# BAT_Simulator.net
KiCad netlist of a schematic drawn in Altium Designer
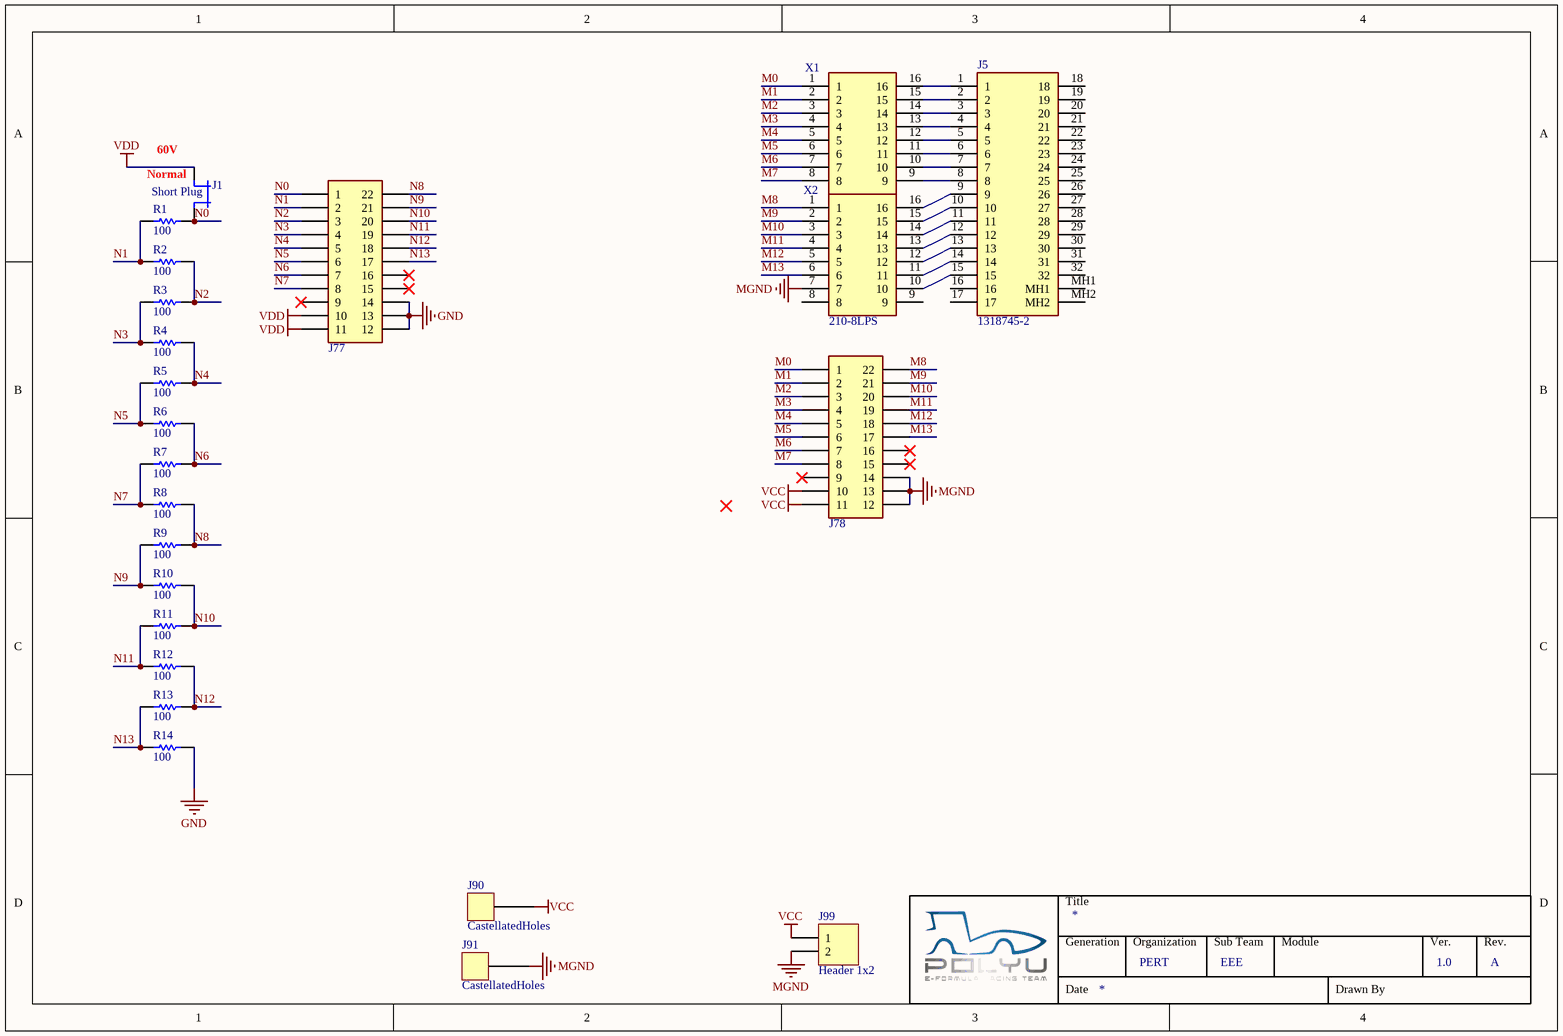
[diagram p0: BAT_Simulator.SchDoc]

(export (version "E")
  (design (tool "Eeschema 10.0.6"))
  (components
    (comp (ref "J1")
      (value "Short Plug")
      (footprint "HDR_1X2_2.54_THD")
      (description "Jumper for shorting two net")
      (libsource (lib "BMS_ShareComponentLibrary") (part "Jumper"))
    )
    (comp (ref "J5")
      (value "1318745-2")
      (footprint "TH025_32P")
      (fields (field (name "MOUSER PART NUMBER") "571-1318745-2"))
      (libsource (lib "BMS_ShareComponentLibrary") (part "TE TH/.25 32P TH"))
    )
    (comp (ref "J77")
      (value "Header 1x5")
      (footprint "HDR_2x11_2.54_THD")
      (description "Header 2x11")
      (libsource (lib "BMS_ShareComponentLibrary") (part "Header 2x11"))
    )
    (comp (ref "J78")
      (value "Header 1x5")
      (footprint "HDR_2x11_2.54_THD")
      (description "Header 2x11")
      (libsource (lib "BMS_ShareComponentLibrary") (part "Header 2x11"))
    )
    (comp (ref "J90")
      (value "CastellatedHoles")
      (footprint "CastellatedHole")
      (libsource (lib "BMS_ShareComponentLibrary") (part "CastellatedHoles"))
    )
    (comp (ref "J91")
      (value "CastellatedHoles")
      (footprint "CastellatedHole")
      (libsource (lib "BMS_ShareComponentLibrary") (part "CastellatedHoles"))
    )
    (comp (ref "J99")
      (value "Header 1x2")
      (footprint "HDR_1X2_2.54_THD")
      (description "Header, 2-Pin")
      (libsource (lib "BMS_ShareComponentLibrary") (part "Header 1x2"))
    )
    (comp (ref "R1")
      (value "100")
      (footprint "2512_SMD_R")
      (description "2512 SMD Resistor")
      (fields (field (name "TOLERANCE") "1%"))
      (libsource (lib "BMS_ShareComponentLibrary") (part "2512_SMD_Resistor"))
    )
    (comp (ref "R2")
      (value "100")
      (footprint "2512_SMD_R")
      (description "2512 SMD Resistor")
      (fields (field (name "TOLERANCE") "1%"))
      (libsource (lib "BMS_ShareComponentLibrary") (part "2512_SMD_Resistor"))
    )
    (comp (ref "R3")
      (value "100")
      (footprint "2512_SMD_R")
      (description "2512 SMD Resistor")
      (fields (field (name "TOLERANCE") "1%"))
      (libsource (lib "BMS_ShareComponentLibrary") (part "2512_SMD_Resistor"))
    )
    (comp (ref "R4")
      (value "100")
      (footprint "2512_SMD_R")
      (description "2512 SMD Resistor")
      (fields (field (name "TOLERANCE") "1%"))
      (libsource (lib "BMS_ShareComponentLibrary") (part "2512_SMD_Resistor"))
    )
    (comp (ref "R5")
      (value "100")
      (footprint "2512_SMD_R")
      (description "2512 SMD Resistor")
      (fields (field (name "TOLERANCE") "1%"))
      (libsource (lib "BMS_ShareComponentLibrary") (part "2512_SMD_Resistor"))
    )
    (comp (ref "R6")
      (value "100")
      (footprint "2512_SMD_R")
      (description "2512 SMD Resistor")
      (fields (field (name "TOLERANCE") "1%"))
      (libsource (lib "BMS_ShareComponentLibrary") (part "2512_SMD_Resistor"))
    )
    (comp (ref "R7")
      (value "100")
      (footprint "2512_SMD_R")
      (description "2512 SMD Resistor")
      (fields (field (name "TOLERANCE") "1%"))
      (libsource (lib "BMS_ShareComponentLibrary") (part "2512_SMD_Resistor"))
    )
    (comp (ref "R8")
      (value "100")
      (footprint "2512_SMD_R")
      (description "2512 SMD Resistor")
      (fields (field (name "TOLERANCE") "1%"))
      (libsource (lib "BMS_ShareComponentLibrary") (part "2512_SMD_Resistor"))
    )
    (comp (ref "R9")
      (value "100")
      (footprint "2512_SMD_R")
      (description "2512 SMD Resistor")
      (fields (field (name "TOLERANCE") "1%"))
      (libsource (lib "BMS_ShareComponentLibrary") (part "2512_SMD_Resistor"))
    )
    (comp (ref "R10")
      (value "100")
      (footprint "2512_SMD_R")
      (description "2512 SMD Resistor")
      (fields (field (name "TOLERANCE") "1%"))
      (libsource (lib "BMS_ShareComponentLibrary") (part "2512_SMD_Resistor"))
    )
    (comp (ref "R11")
      (value "100")
      (footprint "2512_SMD_R")
      (description "2512 SMD Resistor")
      (fields (field (name "TOLERANCE") "1%"))
      (libsource (lib "BMS_ShareComponentLibrary") (part "2512_SMD_Resistor"))
    )
    (comp (ref "R12")
      (value "100")
      (footprint "2512_SMD_R")
      (description "2512 SMD Resistor")
      (fields (field (name "TOLERANCE") "1%"))
      (libsource (lib "BMS_ShareComponentLibrary") (part "2512_SMD_Resistor"))
    )
    (comp (ref "R13")
      (value "100")
      (footprint "2512_SMD_R")
      (description "2512 SMD Resistor")
      (fields (field (name "TOLERANCE") "1%"))
      (libsource (lib "BMS_ShareComponentLibrary") (part "2512_SMD_Resistor"))
    )
    (comp (ref "R14")
      (value "100")
      (footprint "2512_SMD_R")
      (description "2512 SMD Resistor")
      (fields (field (name "TOLERANCE") "1%"))
      (libsource (lib "BMS_ShareComponentLibrary") (part "2512_SMD_Resistor"))
    )
    (comp (ref "X1")
      (value "210-8LPS")
      (footprint "DIP Switch 8Ch")
      (libsource (lib "BMS_ShareComponentLibrary") (part "DIP Switch 8Ch"))
    )
    (comp (ref "X2")
      (value "210-8LPS")
      (footprint "DIP Switch 8Ch")
      (libsource (lib "BMS_ShareComponentLibrary") (part "DIP Switch 8Ch"))
    )
  )
  (nets
    (net (code "1") (name "/M0") (class "Default")
      (node (ref "J78") (pin "1") (pinfunction "1_1") (pintype "passive"))
      (node (ref "X1") (pin "1") (pinfunction "1_1") (pintype "passive"))
    )
    (net (code "2") (name "/M1") (class "Default")
      (node (ref "J78") (pin "2") (pinfunction "2_2") (pintype "passive"))
      (node (ref "X1") (pin "2") (pinfunction "2_2") (pintype "passive"))
    )
    (net (code "3") (name "/M2") (class "Default")
      (node (ref "J78") (pin "3") (pinfunction "3_3") (pintype "passive"))
      (node (ref "X1") (pin "3") (pinfunction "3_3") (pintype "passive"))
    )
    (net (code "4") (name "/M3") (class "Default")
      (node (ref "J78") (pin "4") (pinfunction "4_4") (pintype "passive"))
      (node (ref "X1") (pin "4") (pinfunction "4_4") (pintype "passive"))
    )
    (net (code "5") (name "/M4") (class "Default")
      (node (ref "J78") (pin "5") (pinfunction "5_5") (pintype "passive"))
      (node (ref "X1") (pin "5") (pinfunction "5_5") (pintype "passive"))
    )
    (net (code "6") (name "/M5") (class "Default")
      (node (ref "J78") (pin "6") (pinfunction "6_6") (pintype "passive"))
      (node (ref "X1") (pin "6") (pinfunction "6_6") (pintype "passive"))
    )
    (net (code "7") (name "/M6") (class "Default")
      (node (ref "J78") (pin "7") (pinfunction "7_7") (pintype "passive"))
      (node (ref "X1") (pin "7") (pinfunction "7_7") (pintype "passive"))
    )
    (net (code "8") (name "/M7") (class "Default")
      (node (ref "J78") (pin "8") (pinfunction "8_8") (pintype "passive"))
      (node (ref "X1") (pin "8") (pinfunction "8_8") (pintype "passive"))
    )
    (net (code "9") (name "/M8") (class "Default")
      (node (ref "J78") (pin "22") (pinfunction "22_22") (pintype "passive"))
      (node (ref "X2") (pin "1") (pinfunction "1_1") (pintype "passive"))
    )
    (net (code "10") (name "/M9") (class "Default")
      (node (ref "J78") (pin "21") (pinfunction "21_21") (pintype "passive"))
      (node (ref "X2") (pin "2") (pinfunction "2_2") (pintype "passive"))
    )
    (net (code "11") (name "/M10") (class "Default")
      (node (ref "J78") (pin "20") (pinfunction "20_20") (pintype "passive"))
      (node (ref "X2") (pin "3") (pinfunction "3_3") (pintype "passive"))
    )
    (net (code "12") (name "/M11") (class "Default")
      (node (ref "J78") (pin "19") (pinfunction "19_19") (pintype "passive"))
      (node (ref "X2") (pin "4") (pinfunction "4_4") (pintype "passive"))
    )
    (net (code "13") (name "/M12") (class "Default")
      (node (ref "J78") (pin "18") (pinfunction "18_18") (pintype "passive"))
      (node (ref "X2") (pin "5") (pinfunction "5_5") (pintype "passive"))
    )
    (net (code "14") (name "/M13") (class "Default")
      (node (ref "J78") (pin "17") (pinfunction "17_17") (pintype "passive"))
      (node (ref "X2") (pin "6") (pinfunction "6_6") (pintype "passive"))
    )
    (net (code "15") (name "/N0") (class "Default")
      (node (ref "J1") (pin "2") (pinfunction "2_2") (pintype "passive"))
      (node (ref "J77") (pin "1") (pinfunction "1_1") (pintype "passive"))
      (node (ref "R1") (pin "2") (pinfunction "2_2") (pintype "passive"))
    )
    (net (code "16") (name "/N1") (class "Default")
      (node (ref "J77") (pin "2") (pinfunction "2_2") (pintype "passive"))
      (node (ref "R1") (pin "1") (pinfunction "1_1") (pintype "passive"))
      (node (ref "R2") (pin "1") (pinfunction "1_1") (pintype "passive"))
    )
    (net (code "17") (name "/N2") (class "Default")
      (node (ref "J77") (pin "3") (pinfunction "3_3") (pintype "passive"))
      (node (ref "R2") (pin "2") (pinfunction "2_2") (pintype "passive"))
      (node (ref "R3") (pin "2") (pinfunction "2_2") (pintype "passive"))
    )
    (net (code "18") (name "/N3") (class "Default")
      (node (ref "J77") (pin "4") (pinfunction "4_4") (pintype "passive"))
      (node (ref "R3") (pin "1") (pinfunction "1_1") (pintype "passive"))
      (node (ref "R4") (pin "1") (pinfunction "1_1") (pintype "passive"))
    )
    (net (code "19") (name "/N4") (class "Default")
      (node (ref "J77") (pin "5") (pinfunction "5_5") (pintype "passive"))
      (node (ref "R4") (pin "2") (pinfunction "2_2") (pintype "passive"))
      (node (ref "R5") (pin "2") (pinfunction "2_2") (pintype "passive"))
    )
    (net (code "20") (name "/N5") (class "Default")
      (node (ref "J77") (pin "6") (pinfunction "6_6") (pintype "passive"))
      (node (ref "R5") (pin "1") (pinfunction "1_1") (pintype "passive"))
      (node (ref "R6") (pin "1") (pinfunction "1_1") (pintype "passive"))
    )
    (net (code "21") (name "/N6") (class "Default")
      (node (ref "J77") (pin "7") (pinfunction "7_7") (pintype "passive"))
      (node (ref "R6") (pin "2") (pinfunction "2_2") (pintype "passive"))
      (node (ref "R7") (pin "2") (pinfunction "2_2") (pintype "passive"))
    )
    (net (code "22") (name "/N7") (class "Default")
      (node (ref "J77") (pin "8") (pinfunction "8_8") (pintype "passive"))
      (node (ref "R7") (pin "1") (pinfunction "1_1") (pintype "passive"))
      (node (ref "R8") (pin "1") (pinfunction "1_1") (pintype "passive"))
    )
    (net (code "23") (name "/N8") (class "Default")
      (node (ref "J77") (pin "22") (pinfunction "22_22") (pintype "passive"))
      (node (ref "R8") (pin "2") (pinfunction "2_2") (pintype "passive"))
      (node (ref "R9") (pin "2") (pinfunction "2_2") (pintype "passive"))
    )
    (net (code "24") (name "/N9") (class "Default")
      (node (ref "J77") (pin "21") (pinfunction "21_21") (pintype "passive"))
      (node (ref "R10") (pin "1") (pinfunction "1_1") (pintype "passive"))
      (node (ref "R9") (pin "1") (pinfunction "1_1") (pintype "passive"))
    )
    (net (code "25") (name "/N10") (class "Default")
      (node (ref "J77") (pin "20") (pinfunction "20_20") (pintype "passive"))
      (node (ref "R10") (pin "2") (pinfunction "2_2") (pintype "passive"))
      (node (ref "R11") (pin "2") (pinfunction "2_2") (pintype "passive"))
    )
    (net (code "26") (name "/N11") (class "Default")
      (node (ref "J77") (pin "19") (pinfunction "19_19") (pintype "passive"))
      (node (ref "R11") (pin "1") (pinfunction "1_1") (pintype "passive"))
      (node (ref "R12") (pin "1") (pinfunction "1_1") (pintype "passive"))
    )
    (net (code "27") (name "/N12") (class "Default")
      (node (ref "J77") (pin "18") (pinfunction "18_18") (pintype "passive"))
      (node (ref "R12") (pin "2") (pinfunction "2_2") (pintype "passive"))
      (node (ref "R13") (pin "2") (pinfunction "2_2") (pintype "passive"))
    )
    (net (code "28") (name "/N13") (class "Default")
      (node (ref "J77") (pin "17") (pinfunction "17_17") (pintype "passive"))
      (node (ref "R13") (pin "1") (pinfunction "1_1") (pintype "passive"))
      (node (ref "R14") (pin "1") (pinfunction "1_1") (pintype "passive"))
    )
    (net (code "29") (name "GND") (class "Default")
      (node (ref "J77") (pin "12") (pinfunction "12_12") (pintype "passive"))
      (node (ref "J77") (pin "13") (pinfunction "13_13") (pintype "passive"))
      (node (ref "J77") (pin "14") (pinfunction "14_14") (pintype "passive"))
      (node (ref "R14") (pin "2") (pinfunction "2_2") (pintype "passive"))
    )
    (net (code "30") (name "MGND") (class "Default")
      (node (ref "J78") (pin "12") (pinfunction "12_12") (pintype "passive"))
      (node (ref "J78") (pin "13") (pinfunction "13_13") (pintype "passive"))
      (node (ref "J78") (pin "14") (pinfunction "14_14") (pintype "passive"))
      (node (ref "J91") (pin "1") (pinfunction "1_1") (pintype "passive"))
      (node (ref "J99") (pin "2") (pinfunction "2_2") (pintype "passive"))
      (node (ref "X2") (pin "7") (pinfunction "7_7") (pintype "passive"))
    )
    (net (code "31") (name "Net-(J5-Pad1)") (class "Default")
      (node (ref "J5") (pin "1") (pinfunction "1_1") (pintype "passive"))
      (node (ref "X1") (pin "16") (pinfunction "16_16") (pintype "passive"))
    )
    (net (code "32") (name "Net-(J5-Pad2)") (class "Default")
      (node (ref "J5") (pin "2") (pinfunction "2_2") (pintype "passive"))
      (node (ref "X1") (pin "15") (pinfunction "15_15") (pintype "passive"))
    )
    (net (code "33") (name "Net-(J5-Pad3)") (class "Default")
      (node (ref "J5") (pin "3") (pinfunction "3_3") (pintype "passive"))
      (node (ref "X1") (pin "14") (pinfunction "14_14") (pintype "passive"))
    )
    (net (code "34") (name "Net-(J5-Pad4)") (class "Default")
      (node (ref "J5") (pin "4") (pinfunction "4_4") (pintype "passive"))
      (node (ref "X1") (pin "13") (pinfunction "13_13") (pintype "passive"))
    )
    (net (code "35") (name "Net-(J5-Pad5)") (class "Default")
      (node (ref "J5") (pin "5") (pinfunction "5_5") (pintype "passive"))
      (node (ref "X1") (pin "12") (pinfunction "12_12") (pintype "passive"))
    )
    (net (code "36") (name "Net-(J5-Pad6)") (class "Default")
      (node (ref "J5") (pin "6") (pinfunction "6_6") (pintype "passive"))
      (node (ref "X1") (pin "11") (pinfunction "11_11") (pintype "passive"))
    )
    (net (code "37") (name "Net-(J5-Pad7)") (class "Default")
      (node (ref "J5") (pin "7") (pinfunction "7_7") (pintype "passive"))
      (node (ref "X1") (pin "10") (pinfunction "10_10") (pintype "passive"))
    )
    (net (code "38") (name "Net-(J5-Pad8)") (class "Default")
      (node (ref "J5") (pin "8") (pinfunction "8_8") (pintype "passive"))
      (node (ref "X1") (pin "9") (pinfunction "9_9") (pintype "passive"))
    )
    (net (code "39") (name "Net-(J5-Pad9)") (class "Default")
      (node (ref "J5") (pin "9") (pinfunction "9_9") (pintype "passive"))
      (node (ref "X2") (pin "16") (pinfunction "16_16") (pintype "passive"))
    )
    (net (code "40") (name "Net-(J5-Pad10)") (class "Default")
      (node (ref "J5") (pin "10") (pinfunction "10_10") (pintype "passive"))
      (node (ref "X2") (pin "15") (pinfunction "15_15") (pintype "passive"))
    )
    (net (code "41") (name "Net-(J5-Pad11)") (class "Default")
      (node (ref "J5") (pin "11") (pinfunction "11_11") (pintype "passive"))
      (node (ref "X2") (pin "14") (pinfunction "14_14") (pintype "passive"))
    )
    (net (code "42") (name "Net-(J5-Pad12)") (class "Default")
      (node (ref "J5") (pin "12") (pinfunction "12_12") (pintype "passive"))
      (node (ref "X2") (pin "13") (pinfunction "13_13") (pintype "passive"))
    )
    (net (code "43") (name "Net-(J5-Pad13)") (class "Default")
      (node (ref "J5") (pin "13") (pinfunction "13_13") (pintype "passive"))
      (node (ref "X2") (pin "12") (pinfunction "12_12") (pintype "passive"))
    )
    (net (code "44") (name "Net-(J5-Pad14)") (class "Default")
      (node (ref "J5") (pin "14") (pinfunction "14_14") (pintype "passive"))
      (node (ref "X2") (pin "11") (pinfunction "11_11") (pintype "passive"))
    )
    (net (code "45") (name "Net-(J5-Pad15)") (class "Default")
      (node (ref "J5") (pin "15") (pinfunction "15_15") (pintype "passive"))
      (node (ref "X2") (pin "10") (pinfunction "10_10") (pintype "passive"))
    )
    (net (code "46") (name "VCC") (class "Default")
      (node (ref "J78") (pin "10") (pinfunction "10_10") (pintype "passive"))
      (node (ref "J78") (pin "11") (pinfunction "11_11") (pintype "passive"))
      (node (ref "J90") (pin "1") (pinfunction "1_1") (pintype "passive"))
      (node (ref "J99") (pin "1") (pinfunction "1_1") (pintype "passive"))
    )
    (net (code "47") (name "VDD") (class "Default")
      (node (ref "J1") (pin "1") (pinfunction "1_1") (pintype "passive"))
      (node (ref "J77") (pin "10") (pinfunction "10_10") (pintype "passive"))
      (node (ref "J77") (pin "11") (pinfunction "11_11") (pintype "passive"))
    )
    (net (code "48") (name "unconnected-(J5-Pad16)") (class "Default")
      (node (ref "J5") (pin "16") (pinfunction "16_16") (pintype "passive"))
    )
    (net (code "49") (name "unconnected-(J5-Pad17)") (class "Default")
      (node (ref "J5") (pin "17") (pinfunction "17_17") (pintype "passive"))
    )
    (net (code "50") (name "unconnected-(J5-Pad18)") (class "Default")
      (node (ref "J5") (pin "18") (pinfunction "18_18") (pintype "passive"))
    )
    (net (code "51") (name "unconnected-(J5-Pad19)") (class "Default")
      (node (ref "J5") (pin "19") (pinfunction "19_19") (pintype "passive"))
    )
    (net (code "52") (name "unconnected-(J5-Pad20)") (class "Default")
      (node (ref "J5") (pin "20") (pinfunction "20_20") (pintype "passive"))
    )
    (net (code "53") (name "unconnected-(J5-Pad21)") (class "Default")
      (node (ref "J5") (pin "21") (pinfunction "21_21") (pintype "passive"))
    )
    (net (code "54") (name "unconnected-(J5-Pad22)") (class "Default")
      (node (ref "J5") (pin "22") (pinfunction "22_22") (pintype "passive"))
    )
    (net (code "55") (name "unconnected-(J5-Pad23)") (class "Default")
      (node (ref "J5") (pin "23") (pinfunction "23_23") (pintype "passive"))
    )
    (net (code "56") (name "unconnected-(J5-Pad24)") (class "Default")
      (node (ref "J5") (pin "24") (pinfunction "24_24") (pintype "passive"))
    )
    (net (code "57") (name "unconnected-(J5-Pad25)") (class "Default")
      (node (ref "J5") (pin "25") (pinfunction "25_25") (pintype "passive"))
    )
    (net (code "58") (name "unconnected-(J5-Pad26)") (class "Default")
      (node (ref "J5") (pin "26") (pinfunction "26_26") (pintype "passive"))
    )
    (net (code "59") (name "unconnected-(J5-Pad27)") (class "Default")
      (node (ref "J5") (pin "27") (pinfunction "27_27") (pintype "passive"))
    )
    (net (code "60") (name "unconnected-(J5-Pad28)") (class "Default")
      (node (ref "J5") (pin "28") (pinfunction "28_28") (pintype "passive"))
    )
    (net (code "61") (name "unconnected-(J5-Pad29)") (class "Default")
      (node (ref "J5") (pin "29") (pinfunction "29_29") (pintype "passive"))
    )
    (net (code "62") (name "unconnected-(J5-Pad30)") (class "Default")
      (node (ref "J5") (pin "30") (pinfunction "30_30") (pintype "passive"))
    )
    (net (code "63") (name "unconnected-(J5-Pad31)") (class "Default")
      (node (ref "J5") (pin "31") (pinfunction "31_31") (pintype "passive"))
    )
    (net (code "64") (name "unconnected-(J5-Pad32)") (class "Default")
      (node (ref "J5") (pin "32") (pinfunction "32_32") (pintype "passive"))
    )
    (net (code "65") (name "unconnected-(J5-PadMH1)") (class "Default")
      (node (ref "J5") (pin "MH1") (pinfunction "MH1_MH1") (pintype "passive"))
    )
    (net (code "66") (name "unconnected-(J5-PadMH2)") (class "Default")
      (node (ref "J5") (pin "MH2") (pinfunction "MH2_MH2") (pintype "passive"))
    )
    (net (code "67") (name "unconnected-(J77-Pad9)") (class "Default")
      (node (ref "J77") (pin "9") (pinfunction "9_9") (pintype "passive+no_connect"))
    )
    (net (code "68") (name "unconnected-(J77-Pad15)") (class "Default")
      (node (ref "J77") (pin "15") (pinfunction "15_15") (pintype "passive+no_connect"))
    )
    (net (code "69") (name "unconnected-(J77-Pad16)") (class "Default")
      (node (ref "J77") (pin "16") (pinfunction "16_16") (pintype "passive+no_connect"))
    )
    (net (code "70") (name "unconnected-(J78-Pad9)") (class "Default")
      (node (ref "J78") (pin "9") (pinfunction "9_9") (pintype "passive+no_connect"))
    )
    (net (code "71") (name "unconnected-(J78-Pad15)") (class "Default")
      (node (ref "J78") (pin "15") (pinfunction "15_15") (pintype "passive+no_connect"))
    )
    (net (code "72") (name "unconnected-(J78-Pad16)") (class "Default")
      (node (ref "J78") (pin "16") (pinfunction "16_16") (pintype "passive+no_connect"))
    )
    (net (code "73") (name "unconnected-(X2-Pad8)") (class "Default")
      (node (ref "X2") (pin "8") (pinfunction "8_8") (pintype "passive"))
    )
    (net (code "74") (name "unconnected-(X2-Pad9)") (class "Default")
      (node (ref "X2") (pin "9") (pinfunction "9_9") (pintype "passive"))
    )
  )
)
